# Schematic.net
KiCad netlist of a schematic drawn in Altium Designer
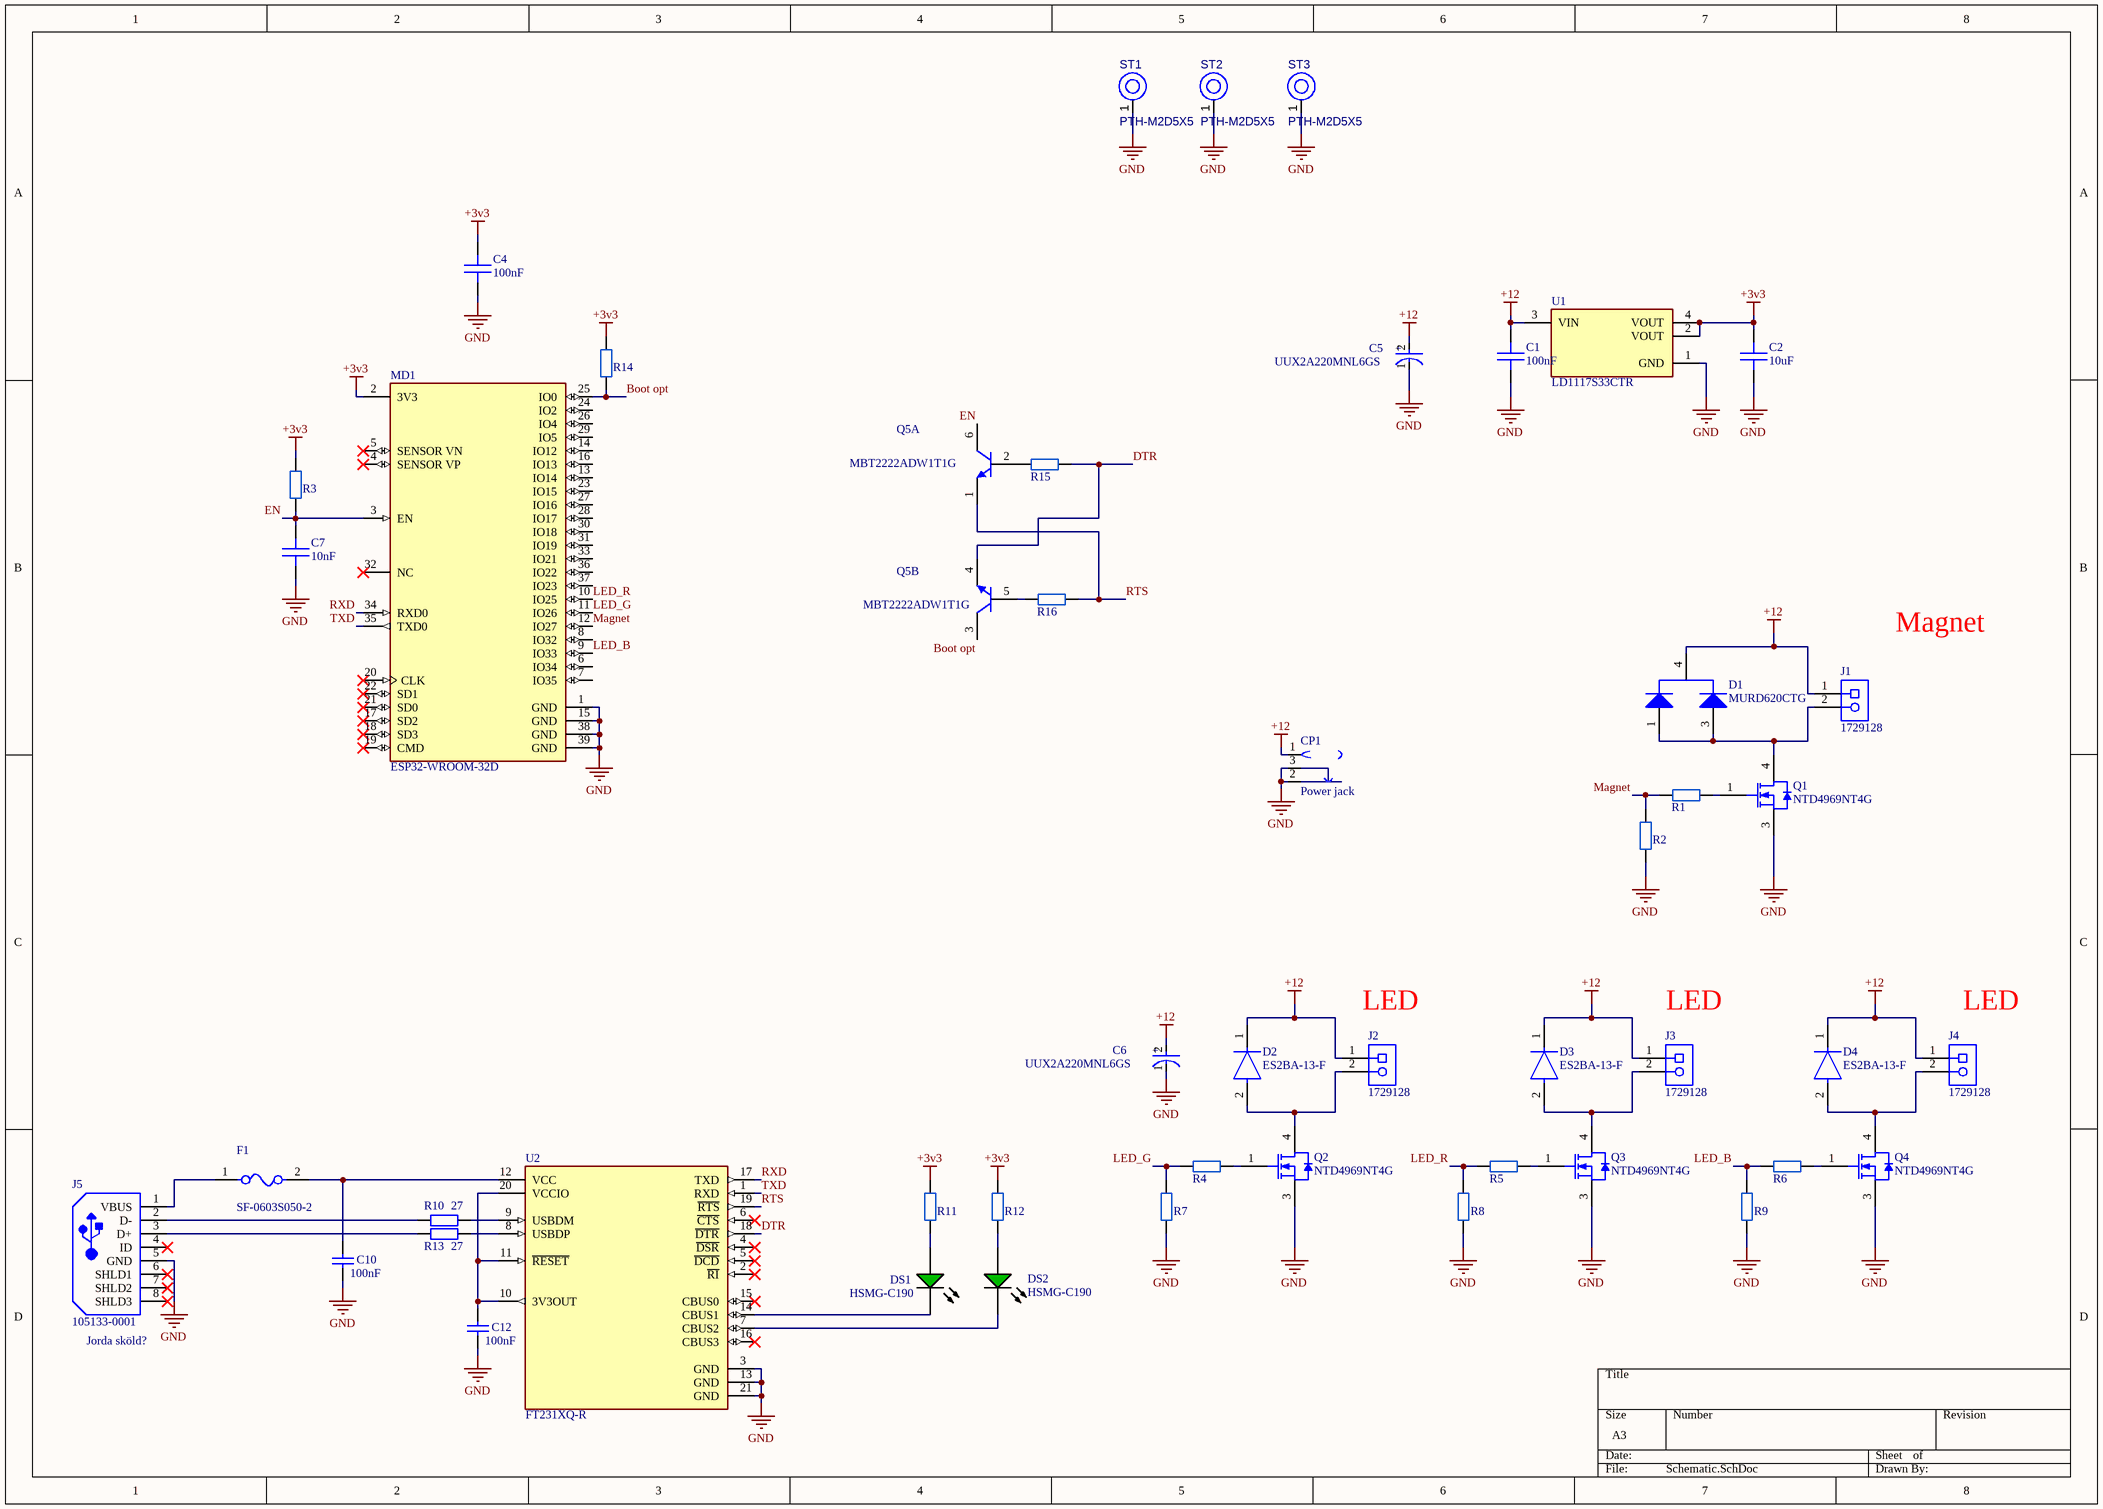
[diagram p0: Schematic.SchDoc]

(export (version "E")
  (design (tool "Eeschema 10.0.6"))
  (components
    (comp (ref "C1")
      (value "100nF")
      (footprint "C0603 (1608)")
      (fields (field (name "Comment") "Cap SMD"))
      (libsource (lib "Moto Symbol Lib") (part "Cap SMD"))
    )
    (comp (ref "C2")
      (value "10uF")
      (footprint "C0603 (1608)")
      (fields (field (name "Comment") "Cap SMD"))
      (libsource (lib "Moto Symbol Lib") (part "Cap SMD"))
    )
    (comp (ref "C4")
      (value "100nF")
      (footprint "C0603 (1608)")
      (fields (field (name "Comment") "Cap SMD"))
      (libsource (lib "Moto Symbol Lib") (part "Cap SMD"))
    )
    (comp (ref "C5")
      (value "UUX2A220MNL6GS")
      (footprint "FP-UUX2A220MNL6GS-MFG")
      (description "CAP ALUM 22UF 20% 100V SMD")
      (fields (field (name "TOLERANCE") "20%"))
      (libsource (lib "Altium Content Vault") (part "cf48714ba7e38822c1575c7ec0b6d1f"))
    )
    (comp (ref "C6")
      (value "UUX2A220MNL6GS")
      (footprint "FP-UUX2A220MNL6GS-MFG")
      (description "CAP ALUM 22UF 20% 100V SMD")
      (fields (field (name "TOLERANCE") "20%"))
      (libsource (lib "Altium Content Vault") (part "cf48714ba7e38822c1575c7ec0b6d1f"))
    )
    (comp (ref "C7")
      (value "10nF")
      (footprint "C0603 (1608)")
      (fields (field (name "Comment") "Cap SMD"))
      (libsource (lib "Moto Symbol Lib") (part "Cap SMD"))
    )
    (comp (ref "C10")
      (value "100nF")
      (footprint "C0603 (1608)")
      (description "Capacitor")
      (fields (field (name "PUBLISHER") "Altium Limited"))
      (libsource (lib "Miscellaneous Devices") (part "Cap"))
    )
    (comp (ref "C12")
      (value "100nF")
      (footprint "C0603 (1608)")
      (description "Capacitor")
      (fields (field (name "PUBLISHER") "Altium Limited"))
      (libsource (lib "Miscellaneous Devices") (part "Cap"))
    )
    (comp (ref "CP1")
      (value "Power jack")
      (footprint "CLIFF SMD KLD-0202 BARRELL JACK DC CONNECTOR 2.1mm")
      (description "Surface mounted DC barrell jack, KLD-0202 design")
      (libsource (lib "lokalib") (part "Barrel jack KLD-0202"))
    )
    (comp (ref "D1")
      (value "MURD620CTG")
      (footprint "ONSC-DPAK-3-369C-01_V")
      (description "SWITCHMODE(TM) Power Rectifier, 3-Pin DPAK, Pb-Free, Tube")
      (fields (field (name "MANUFACTURER") "On Semiconductor"))
      (libsource (lib "Altium Content Vault") (part "ONSC-D-A1A3K4-3_B"))
    )
    (comp (ref "D2")
      (value "ES2BA-13-F")
      (footprint "FP-SMA-MFG")
      (description "DIODE GEN PURP 100V 2A SMA")
      (fields
        (field (name "MANUFACTURER") "Diodes Inc.")
        (field (name "OCTOPART") "https://octopart.com/es2ba-13-f-diodes+inc.-14402013")
      )
      (libsource (lib "Altium Content Vault") (part "d7152d700b627762746794eb795d46e"))
    )
    (comp (ref "D3")
      (value "ES2BA-13-F")
      (footprint "FP-SMA-MFG")
      (description "DIODE GEN PURP 100V 2A SMA")
      (fields
        (field (name "MANUFACTURER") "Diodes Inc.")
        (field (name "OCTOPART") "https://octopart.com/es2ba-13-f-diodes+inc.-14402013")
      )
      (libsource (lib "Altium Content Vault") (part "d7152d700b627762746794eb795d46e"))
    )
    (comp (ref "D4")
      (value "ES2BA-13-F")
      (footprint "FP-SMA-MFG")
      (description "DIODE GEN PURP 100V 2A SMA")
      (fields
        (field (name "MANUFACTURER") "Diodes Inc.")
        (field (name "OCTOPART") "https://octopart.com/es2ba-13-f-diodes+inc.-14402013")
      )
      (libsource (lib "Altium Content Vault") (part "d7152d700b627762746794eb795d46e"))
    )
    (comp (ref "DS1")
      (value "HSMG-C190")
      (footprint "AVAG-HSMX-C190_V")
      (description "Chip LED, Green, 2.2 V, -40 to 85 degC, 2-Pin SMD, RoHS, Tape and Reel")
      (libsource (lib "Altium Content Vault") (part "LED-GREEN-AK-2"))
    )
    (comp (ref "DS2")
      (value "HSMG-C190")
      (footprint "AVAG-HSMX-C190_V")
      (description "Chip LED, Green, 2.2 V, -40 to 85 degC, 2-Pin SMD, RoHS, Tape and Reel")
      (libsource (lib "Altium Content Vault") (part "LED-GREEN-AK-2"))
    )
    (comp (ref "F1")
      (value "SF-0603S050-2")
      (footprint "FP-SF-0603S-MFG")
      (description "FUSE BOARD MNT 500MA 50VDC 0603")
      (fields
        (field (name "MANUFACTURER") "Bourns Inc.")
        (field (name "OCTOPART") "https://octopart.com/sf-0603s050-2-bourns-10486821")
      )
      (libsource (lib "Altium Content Vault") (part "5bcf9b9f640e542cf0359d10258e979"))
    )
    (comp (ref "J1")
      (value "1729128")
      (footprint "PHOE-1729128-2_V")
      (description "PCB Terminal Block, 13.5 A, 400 V, 2-Pin THD, RoHS, Bulk")
      (fields (field (name "MANUFACTURER") "Phoenix Contact"))
      (libsource (lib "Altium Content Vault") (part "CN-2P-F-R2"))
    )
    (comp (ref "J2")
      (value "1729128")
      (footprint "PHOE-1729128-2_V")
      (description "PCB Terminal Block, 13.5 A, 400 V, 2-Pin THD, RoHS, Bulk")
      (fields (field (name "MANUFACTURER") "Phoenix Contact"))
      (libsource (lib "Altium Content Vault") (part "CN-2P-F-R2"))
    )
    (comp (ref "J3")
      (value "1729128")
      (footprint "PHOE-1729128-2_V")
      (description "PCB Terminal Block, 13.5 A, 400 V, 2-Pin THD, RoHS, Bulk")
      (fields (field (name "MANUFACTURER") "Phoenix Contact"))
      (libsource (lib "Altium Content Vault") (part "CN-2P-F-R2"))
    )
    (comp (ref "J4")
      (value "1729128")
      (footprint "PHOE-1729128-2_V")
      (description "PCB Terminal Block, 13.5 A, 400 V, 2-Pin THD, RoHS, Bulk")
      (fields (field (name "MANUFACTURER") "Phoenix Contact"))
      (libsource (lib "Altium Content Vault") (part "CN-2P-F-R2"))
    )
    (comp (ref "J5")
      (value "105133-0001")
      (footprint "MOLX-105133-0001_V")
      (description "Micro-USB B Receptacle, Vertical, -30 to 85 degC, 5-Pin SMD, RoHS, Tape and Reel")
      (fields (field (name "MANUFACTURER") "Molex"))
      (libsource (lib "Altium Content Vault") (part "USB-5-3SHLD"))
    )
    (comp (ref "MD1")
      (value "ESP32-WROOM-32D")
      (footprint "FP-ESP32-WROOM-32D-MFG")
      (description "WIFI MODULE 32MBITS SPI FLASH")
      (fields
        (field (name "OCTOPART") "https://octopart.com/esp32-wroom-32d-espressif+systems-91040050")
        (field (name "MANUFACTURER") "Espressif Systems")
      )
      (libsource (lib "Altium Content Vault") (part "a031a76f8c27026a7a7f4657ff233a3"))
    )
    (comp (ref "Q1")
      (value "NTD4969NT4G")
      (footprint "ONSC-DPAK-3-369AA-01_V")
      (description "Power MOSFET, 30 V, 41 A, Single N-Channel, 3-Pin DPAK, Pb-Free, Tape and Reel")
      (fields (field (name "MANUFACTURER") "On Semiconductor"))
      (libsource (lib "Altium Content Vault") (part "ONSC-NMOS-G1S3D4-3_B"))
    )
    (comp (ref "Q2")
      (value "NTD4969NT4G")
      (footprint "ONSC-DPAK-3-369AA-01_V")
      (description "Power MOSFET, 30 V, 41 A, Single N-Channel, 3-Pin DPAK, Pb-Free, Tape and Reel")
      (fields (field (name "MANUFACTURER") "On Semiconductor"))
      (libsource (lib "Altium Content Vault") (part "ONSC-NMOS-G1S3D4-3_B"))
    )
    (comp (ref "Q3")
      (value "NTD4969NT4G")
      (footprint "ONSC-DPAK-3-369AA-01_V")
      (description "Power MOSFET, 30 V, 41 A, Single N-Channel, 3-Pin DPAK, Pb-Free, Tape and Reel")
      (fields (field (name "MANUFACTURER") "On Semiconductor"))
      (libsource (lib "Altium Content Vault") (part "ONSC-NMOS-G1S3D4-3_B"))
    )
    (comp (ref "Q4")
      (value "NTD4969NT4G")
      (footprint "ONSC-DPAK-3-369AA-01_V")
      (description "Power MOSFET, 30 V, 41 A, Single N-Channel, 3-Pin DPAK, Pb-Free, Tape and Reel")
      (fields (field (name "MANUFACTURER") "On Semiconductor"))
      (libsource (lib "Altium Content Vault") (part "ONSC-NMOS-G1S3D4-3_B"))
    )
    (comp (ref "Q5")
      (value "MBT2222ADW1T1G")
      (footprint "ONSC-SOT-363-6-419B-02_V")
      (description "General Purpose Transistor, NPN Silicon, 6-Pin SOT-363, Pb-Free, Tape and Reel")
      (fields (field (name "MANUFACTURER") "On Semiconductor"))
      (libsource (lib "Altium Content Vault") (part "ONSC-NPN_NPN-6_F"))
    )
    (comp (ref "R1")
      (value "Res")
      (footprint "R0603 (1608)")
      (libsource (lib "Moto Symbol Lib") (part "Resistor EU"))
    )
    (comp (ref "R2")
      (value "Res")
      (footprint "R0603 (1608)")
      (libsource (lib "Moto Symbol Lib") (part "Resistor EU"))
    )
    (comp (ref "R3")
      (value "Res")
      (footprint "R0603 (1608)")
      (libsource (lib "Moto Symbol Lib") (part "Resistor EU"))
    )
    (comp (ref "R4")
      (value "Res")
      (footprint "R0603 (1608)")
      (libsource (lib "Moto Symbol Lib") (part "Resistor EU"))
    )
    (comp (ref "R5")
      (value "Res")
      (footprint "R0603 (1608)")
      (libsource (lib "Moto Symbol Lib") (part "Resistor EU"))
    )
    (comp (ref "R6")
      (value "Res")
      (footprint "R0603 (1608)")
      (libsource (lib "Moto Symbol Lib") (part "Resistor EU"))
    )
    (comp (ref "R7")
      (value "Res")
      (footprint "R0603 (1608)")
      (libsource (lib "Moto Symbol Lib") (part "Resistor EU"))
    )
    (comp (ref "R8")
      (value "Res")
      (footprint "R0603 (1608)")
      (libsource (lib "Moto Symbol Lib") (part "Resistor EU"))
    )
    (comp (ref "R9")
      (value "Res")
      (footprint "R0603 (1608)")
      (libsource (lib "Moto Symbol Lib") (part "Resistor EU"))
    )
    (comp (ref "R10")
      (value "27")
      (footprint "R0603 (1608)")
      (description "Resistor")
      (fields (field (name "PUBLISHER") "Altium Limited"))
      (libsource (lib "Miscellaneous Devices") (part "Res2"))
    )
    (comp (ref "R11")
      (value "Res")
      (footprint "R0603 (1608)")
      (libsource (lib "Moto Symbol Lib") (part "Resistor EU"))
    )
    (comp (ref "R12")
      (value "Res")
      (footprint "R0603 (1608)")
      (libsource (lib "Moto Symbol Lib") (part "Resistor EU"))
    )
    (comp (ref "R13")
      (value "27")
      (footprint "R0603 (1608)")
      (description "Resistor")
      (fields (field (name "PUBLISHER") "Altium Limited"))
      (libsource (lib "Miscellaneous Devices") (part "Res2"))
    )
    (comp (ref "R14")
      (value "Res")
      (footprint "R0603 (1608)")
      (libsource (lib "Moto Symbol Lib") (part "Resistor EU"))
    )
    (comp (ref "R15")
      (value "Res")
      (footprint "R0603 (1608)")
      (libsource (lib "Moto Symbol Lib") (part "Resistor EU"))
    )
    (comp (ref "R16")
      (value "Res")
      (footprint "R0603 (1608)")
      (libsource (lib "Moto Symbol Lib") (part "Resistor EU"))
    )
    (comp (ref "ST1")
      (value "PTH-M2D5X5")
      (footprint "PTH-M2D5X5")
      (description "M2 PTH (2.5mm), 5mm pad")
      (libsource (lib "ETA - E-sektionsens Teletekniska Avdelning") (part "CMP-00028-00000-1"))
    )
    (comp (ref "ST2")
      (value "PTH-M2D5X5")
      (footprint "PTH-M2D5X5")
      (description "M2 PTH (2.5mm), 5mm pad")
      (libsource (lib "ETA - E-sektionsens Teletekniska Avdelning") (part "CMP-00028-00000-1"))
    )
    (comp (ref "ST3")
      (value "PTH-M2D5X5")
      (footprint "PTH-M2D5X5")
      (description "M2 PTH (2.5mm), 5mm pad")
      (libsource (lib "ETA - E-sektionsens Teletekniska Avdelning") (part "CMP-00028-00000-1"))
    )
    (comp (ref "U1")
      (value "LD1117S33CTR")
      (footprint "FP-SOT-223-0046067_14-MFG")
      (description "IC REG LINEAR 3.3V 800MA SOT223")
      (libsource (lib "Altium Content Vault") (part "7818869c5c16ceab15634627166a29d"))
    )
    (comp (ref "U2")
      (value "FT231XQ-R")
      (footprint "FP-QFN-20-MFG")
      (description "IC USB SERIAL FULL UART 20QFN")
      (libsource (lib "Altium Content Vault") (part "1a58eaec777a01ae16a7011961d8d4e"))
    )
  )
  (nets
    (net (code "1") (name "+3v3") (class "Default")
      (node (ref "C2") (pin "2") (pinfunction "2_2") (pintype "power_in"))
      (node (ref "C4") (pin "2") (pinfunction "2_2") (pintype "power_in"))
      (node (ref "MD1") (pin "2") (pinfunction "3V3_2") (pintype "power_in"))
      (node (ref "R11") (pin "2") (pinfunction "2_2") (pintype "power_in"))
      (node (ref "R12") (pin "2") (pinfunction "2_2") (pintype "power_in"))
      (node (ref "R14") (pin "1") (pinfunction "1_1") (pintype "power_in"))
      (node (ref "R3") (pin "1") (pinfunction "1_1") (pintype "power_in"))
      (node (ref "U1") (pin "2") (pinfunction "VOUT_2") (pintype "power_in"))
      (node (ref "U1") (pin "4") (pinfunction "VOUT_4") (pintype "power_in"))
    )
    (net (code "2") (name "+12") (class "Default")
      (node (ref "C1") (pin "2") (pinfunction "2_2") (pintype "power_in"))
      (node (ref "C5") (pin "2") (pinfunction "A_2") (pintype "passive"))
      (node (ref "C6") (pin "2") (pinfunction "A_2") (pintype "passive"))
      (node (ref "CP1") (pin "1") (pintype "passive"))
      (node (ref "D1") (pin "4") (pinfunction "K_4") (pintype "passive"))
      (node (ref "D2") (pin "1") (pinfunction "C_1") (pintype "passive"))
      (node (ref "D3") (pin "1") (pinfunction "C_1") (pintype "passive"))
      (node (ref "D4") (pin "1") (pinfunction "C_1") (pintype "passive"))
      (node (ref "J1") (pin "1") (pinfunction "1_1") (pintype "passive"))
      (node (ref "J2") (pin "1") (pinfunction "1_1") (pintype "passive"))
      (node (ref "J3") (pin "1") (pinfunction "1_1") (pintype "passive"))
      (node (ref "J4") (pin "1") (pinfunction "1_1") (pintype "passive"))
      (node (ref "U1") (pin "3") (pinfunction "VIN_3") (pintype "power_in"))
    )
    (net (code "3") (name "/Boot opt") (class "Default")
      (node (ref "MD1") (pin "25") (pinfunction "IO0_25") (pintype "bidirectional"))
      (node (ref "Q5") (pin "3") (pinfunction "C_3") (pintype "passive"))
      (node (ref "R14") (pin "2") (pinfunction "2_2") (pintype "power_in"))
    )
    (net (code "4") (name "/DTR") (class "Default")
      (node (ref "Q5") (pin "4") (pinfunction "E_4") (pintype "passive"))
      (node (ref "R15") (pin "2") (pinfunction "2_2") (pintype "power_in"))
      (node (ref "U2") (pin "18") (pinfunction "~{DTR}_18") (pintype "output"))
    )
    (net (code "5") (name "/EN") (class "Default")
      (node (ref "C7") (pin "2") (pinfunction "2_2") (pintype "power_in"))
      (node (ref "MD1") (pin "3") (pinfunction "EN_3") (pintype "input"))
      (node (ref "Q5") (pin "6") (pinfunction "C_6") (pintype "passive"))
      (node (ref "R3") (pin "2") (pinfunction "2_2") (pintype "power_in"))
    )
    (net (code "6") (name "/LED_B") (class "Default")
      (node (ref "MD1") (pin "9") (pinfunction "IO33_9") (pintype "bidirectional"))
      (node (ref "R6") (pin "2") (pinfunction "2_2") (pintype "power_in"))
      (node (ref "R9") (pin "2") (pinfunction "2_2") (pintype "power_in"))
    )
    (net (code "7") (name "/LED_G") (class "Default")
      (node (ref "MD1") (pin "11") (pinfunction "IO26_11") (pintype "bidirectional"))
      (node (ref "R4") (pin "2") (pinfunction "2_2") (pintype "power_in"))
      (node (ref "R7") (pin "2") (pinfunction "2_2") (pintype "power_in"))
    )
    (net (code "8") (name "/LED_R") (class "Default")
      (node (ref "MD1") (pin "10") (pinfunction "IO25_10") (pintype "bidirectional"))
      (node (ref "R5") (pin "2") (pinfunction "2_2") (pintype "power_in"))
      (node (ref "R8") (pin "1") (pinfunction "1_1") (pintype "power_in"))
    )
    (net (code "9") (name "/Magnet") (class "Default")
      (node (ref "MD1") (pin "12") (pinfunction "IO27_12") (pintype "bidirectional"))
      (node (ref "R1") (pin "2") (pinfunction "2_2") (pintype "power_in"))
      (node (ref "R2") (pin "2") (pinfunction "2_2") (pintype "power_in"))
    )
    (net (code "10") (name "/RTS") (class "Default")
      (node (ref "Q5") (pin "1") (pinfunction "E_1") (pintype "passive"))
      (node (ref "R16") (pin "2") (pinfunction "2_2") (pintype "power_in"))
      (node (ref "U2") (pin "19") (pinfunction "~{RTS}_19") (pintype "output"))
    )
    (net (code "11") (name "/RXD") (class "Default")
      (node (ref "MD1") (pin "34") (pinfunction "RXD0_34") (pintype "input"))
      (node (ref "U2") (pin "17") (pinfunction "TXD_17") (pintype "output"))
    )
    (net (code "12") (name "/TXD") (class "Default")
      (node (ref "MD1") (pin "35") (pinfunction "TXD0_35") (pintype "output"))
      (node (ref "U2") (pin "1") (pinfunction "RXD_1") (pintype "input"))
    )
    (net (code "13") (name "GND") (class "Default")
      (node (ref "C1") (pin "1") (pinfunction "1_1") (pintype "power_in"))
      (node (ref "C10") (pin "1") (pinfunction "1_1") (pintype "passive"))
      (node (ref "C12") (pin "1") (pinfunction "1_1") (pintype "passive"))
      (node (ref "C2") (pin "1") (pinfunction "1_1") (pintype "power_in"))
      (node (ref "C4") (pin "1") (pinfunction "1_1") (pintype "power_in"))
      (node (ref "C5") (pin "1") (pinfunction "C_1") (pintype "passive"))
      (node (ref "C6") (pin "1") (pinfunction "C_1") (pintype "passive"))
      (node (ref "C7") (pin "1") (pinfunction "1_1") (pintype "power_in"))
      (node (ref "CP1") (pin "2") (pintype "passive"))
      (node (ref "CP1") (pin "3") (pintype "passive"))
      (node (ref "J5") (pin "5") (pinfunction "GND_5") (pintype "passive"))
      (node (ref "MD1") (pin "1") (pinfunction "GND_1") (pintype "power_in"))
      (node (ref "MD1") (pin "15") (pinfunction "GND_15") (pintype "power_in"))
      (node (ref "MD1") (pin "38") (pinfunction "GND_38") (pintype "power_in"))
      (node (ref "MD1") (pin "39") (pinfunction "GND_39") (pintype "power_in"))
      (node (ref "Q1") (pin "3") (pinfunction "S_3") (pintype "passive"))
      (node (ref "Q2") (pin "3") (pinfunction "S_3") (pintype "passive"))
      (node (ref "Q3") (pin "3") (pinfunction "S_3") (pintype "passive"))
      (node (ref "Q4") (pin "3") (pinfunction "S_3") (pintype "passive"))
      (node (ref "R2") (pin "1") (pinfunction "1_1") (pintype "power_in"))
      (node (ref "R7") (pin "1") (pinfunction "1_1") (pintype "power_in"))
      (node (ref "R8") (pin "2") (pinfunction "2_2") (pintype "power_in"))
      (node (ref "R9") (pin "1") (pinfunction "1_1") (pintype "power_in"))
      (node (ref "ST1") (pin "1") (pinfunction "H1_1") (pintype "passive"))
      (node (ref "ST2") (pin "1") (pinfunction "H1_1") (pintype "passive"))
      (node (ref "ST3") (pin "1") (pinfunction "H1_1") (pintype "passive"))
      (node (ref "U1") (pin "1") (pinfunction "GND_1") (pintype "power_in"))
      (node (ref "U2") (pin "13") (pinfunction "GND_13") (pintype "open_emitter"))
      (node (ref "U2") (pin "21") (pinfunction "GND_21") (pintype "power_in"))
      (node (ref "U2") (pin "3") (pinfunction "GND_3") (pintype "power_in"))
    )
    (net (code "14") (name "Net-(D1-A1)") (class "Default")
      (node (ref "D1") (pin "1") (pinfunction "A1_1") (pintype "passive"))
      (node (ref "D1") (pin "3") (pinfunction "A2_3") (pintype "passive"))
      (node (ref "J1") (pin "2") (pinfunction "2_2") (pintype "passive"))
      (node (ref "Q1") (pin "4") (pinfunction "D_4") (pintype "passive"))
    )
    (net (code "15") (name "Net-(D2-A)") (class "Default")
      (node (ref "D2") (pin "2") (pinfunction "A_2") (pintype "passive"))
      (node (ref "J2") (pin "2") (pinfunction "2_2") (pintype "passive"))
      (node (ref "Q2") (pin "4") (pinfunction "D_4") (pintype "passive"))
    )
    (net (code "16") (name "Net-(D3-A)") (class "Default")
      (node (ref "D3") (pin "2") (pinfunction "A_2") (pintype "passive"))
      (node (ref "J3") (pin "2") (pinfunction "2_2") (pintype "passive"))
      (node (ref "Q3") (pin "4") (pinfunction "D_4") (pintype "passive"))
    )
    (net (code "17") (name "Net-(D4-A)") (class "Default")
      (node (ref "D4") (pin "2") (pinfunction "A_2") (pintype "passive"))
      (node (ref "J4") (pin "2") (pinfunction "2_2") (pintype "passive"))
      (node (ref "Q4") (pin "4") (pinfunction "D_4") (pintype "passive"))
    )
    (net (code "18") (name "Net-(DS1-A)") (class "Default")
      (node (ref "DS1") (pin "1") (pinfunction "A_1") (pintype "passive"))
      (node (ref "R11") (pin "1") (pinfunction "1_1") (pintype "power_in"))
    )
    (net (code "19") (name "Net-(DS1-K)") (class "Default")
      (node (ref "DS1") (pin "2") (pinfunction "K_2") (pintype "passive"))
      (node (ref "U2") (pin "14") (pinfunction "CBUS1_14") (pintype "bidirectional"))
    )
    (net (code "20") (name "Net-(DS2-A)") (class "Default")
      (node (ref "DS2") (pin "1") (pinfunction "A_1") (pintype "passive"))
      (node (ref "R12") (pin "1") (pinfunction "1_1") (pintype "power_in"))
    )
    (net (code "21") (name "Net-(DS2-K)") (class "Default")
      (node (ref "DS2") (pin "2") (pinfunction "K_2") (pintype "passive"))
      (node (ref "U2") (pin "7") (pinfunction "CBUS2_7") (pintype "bidirectional"))
    )
    (net (code "22") (name "Net-(J5-D+)") (class "Default")
      (node (ref "J5") (pin "3") (pinfunction "D+_3") (pintype "passive"))
      (node (ref "R13") (pin "1") (pinfunction "1_1") (pintype "passive"))
    )
    (net (code "23") (name "Net-(J5-D-)") (class "Default")
      (node (ref "J5") (pin "2") (pinfunction "D-_2") (pintype "passive"))
      (node (ref "R10") (pin "1") (pinfunction "1_1") (pintype "passive"))
    )
    (net (code "24") (name "Net-(J5-VBUS)") (class "Default")
      (node (ref "F1") (pin "1") (pinfunction "1_1") (pintype "passive"))
      (node (ref "J5") (pin "1") (pinfunction "VBUS_1") (pintype "passive"))
    )
    (net (code "25") (name "Net-(Q1-G)") (class "Default")
      (node (ref "Q1") (pin "1") (pinfunction "G_1") (pintype "passive"))
      (node (ref "R1") (pin "1") (pinfunction "1_1") (pintype "power_in"))
    )
    (net (code "26") (name "Net-(Q2-G)") (class "Default")
      (node (ref "Q2") (pin "1") (pinfunction "G_1") (pintype "passive"))
      (node (ref "R4") (pin "1") (pinfunction "1_1") (pintype "power_in"))
    )
    (net (code "27") (name "Net-(Q3-G)") (class "Default")
      (node (ref "Q3") (pin "1") (pinfunction "G_1") (pintype "passive"))
      (node (ref "R5") (pin "1") (pinfunction "1_1") (pintype "power_in"))
    )
    (net (code "28") (name "Net-(Q4-G)") (class "Default")
      (node (ref "Q4") (pin "1") (pinfunction "G_1") (pintype "passive"))
      (node (ref "R6") (pin "1") (pinfunction "1_1") (pintype "power_in"))
    )
    (net (code "29") (name "Net-(Q5A-B)") (class "Default")
      (node (ref "Q5") (pin "2") (pinfunction "B_2") (pintype "passive"))
      (node (ref "R15") (pin "1") (pinfunction "1_1") (pintype "power_in"))
    )
    (net (code "30") (name "Net-(Q5B-B)") (class "Default")
      (node (ref "Q5") (pin "5") (pinfunction "B_5") (pintype "passive"))
      (node (ref "R16") (pin "1") (pinfunction "1_1") (pintype "power_in"))
    )
    (net (code "31") (name "Net-(U2-3V3OUT)") (class "Default")
      (node (ref "C12") (pin "2") (pinfunction "2_2") (pintype "passive"))
      (node (ref "U2") (pin "10") (pinfunction "3V3OUT_10") (pintype "output"))
      (node (ref "U2") (pin "11") (pinfunction "~{RESET}_11") (pintype "input"))
      (node (ref "U2") (pin "20") (pinfunction "VCCIO_20") (pintype "power_in"))
    )
    (net (code "32") (name "Net-(U2-USBDM)") (class "Default")
      (node (ref "R10") (pin "2") (pinfunction "2_2") (pintype "passive"))
      (node (ref "U2") (pin "9") (pinfunction "USBDM_9") (pintype "input"))
    )
    (net (code "33") (name "Net-(U2-USBDP)") (class "Default")
      (node (ref "R13") (pin "2") (pinfunction "2_2") (pintype "passive"))
      (node (ref "U2") (pin "8") (pinfunction "USBDP_8") (pintype "input"))
    )
    (net (code "34") (name "Net-(U2-VCC)") (class "Default")
      (node (ref "C10") (pin "2") (pinfunction "2_2") (pintype "passive"))
      (node (ref "F1") (pin "2") (pinfunction "2_2") (pintype "passive"))
      (node (ref "U2") (pin "12") (pinfunction "VCC_12") (pintype "power_in"))
    )
    (net (code "35") (name "unconnected-(J5-ID-Pad4)") (class "Default")
      (node (ref "J5") (pin "4") (pinfunction "ID_4") (pintype "passive+no_connect"))
    )
    (net (code "36") (name "unconnected-(J5-SHLD1-Pad6)") (class "Default")
      (node (ref "J5") (pin "6") (pinfunction "SHLD1_6") (pintype "passive+no_connect"))
    )
    (net (code "37") (name "unconnected-(J5-SHLD2-Pad7)") (class "Default")
      (node (ref "J5") (pin "7") (pinfunction "SHLD2_7") (pintype "passive+no_connect"))
    )
    (net (code "38") (name "unconnected-(J5-SHLD3-Pad8)") (class "Default")
      (node (ref "J5") (pin "8") (pinfunction "SHLD3_8") (pintype "passive+no_connect"))
    )
    (net (code "39") (name "unconnected-(MD1-CLK-Pad20)") (class "Default")
      (node (ref "MD1") (pin "20") (pinfunction "CLK_20") (pintype "input+no_connect"))
    )
    (net (code "40") (name "unconnected-(MD1-CMD-Pad19)") (class "Default")
      (node (ref "MD1") (pin "19") (pinfunction "CMD_19") (pintype "bidirectional+no_connect"))
    )
    (net (code "41") (name "unconnected-(MD1-IO2-Pad24)") (class "Default")
      (node (ref "MD1") (pin "24") (pinfunction "IO2_24") (pintype "bidirectional"))
    )
    (net (code "42") (name "unconnected-(MD1-IO4-Pad26)") (class "Default")
      (node (ref "MD1") (pin "26") (pinfunction "IO4_26") (pintype "bidirectional"))
    )
    (net (code "43") (name "unconnected-(MD1-IO5-Pad29)") (class "Default")
      (node (ref "MD1") (pin "29") (pinfunction "IO5_29") (pintype "bidirectional"))
    )
    (net (code "44") (name "unconnected-(MD1-IO12-Pad14)") (class "Default")
      (node (ref "MD1") (pin "14") (pinfunction "IO12_14") (pintype "bidirectional"))
    )
    (net (code "45") (name "unconnected-(MD1-IO13-Pad16)") (class "Default")
      (node (ref "MD1") (pin "16") (pinfunction "IO13_16") (pintype "bidirectional"))
    )
    (net (code "46") (name "unconnected-(MD1-IO14-Pad13)") (class "Default")
      (node (ref "MD1") (pin "13") (pinfunction "IO14_13") (pintype "bidirectional"))
    )
    (net (code "47") (name "unconnected-(MD1-IO15-Pad23)") (class "Default")
      (node (ref "MD1") (pin "23") (pinfunction "IO15_23") (pintype "bidirectional"))
    )
    (net (code "48") (name "unconnected-(MD1-IO16-Pad27)") (class "Default")
      (node (ref "MD1") (pin "27") (pinfunction "IO16_27") (pintype "bidirectional"))
    )
    (net (code "49") (name "unconnected-(MD1-IO17-Pad28)") (class "Default")
      (node (ref "MD1") (pin "28") (pinfunction "IO17_28") (pintype "bidirectional"))
    )
    (net (code "50") (name "unconnected-(MD1-IO18-Pad30)") (class "Default")
      (node (ref "MD1") (pin "30") (pinfunction "IO18_30") (pintype "bidirectional"))
    )
    (net (code "51") (name "unconnected-(MD1-IO19-Pad31)") (class "Default")
      (node (ref "MD1") (pin "31") (pinfunction "IO19_31") (pintype "bidirectional"))
    )
    (net (code "52") (name "unconnected-(MD1-IO21-Pad33)") (class "Default")
      (node (ref "MD1") (pin "33") (pinfunction "IO21_33") (pintype "bidirectional"))
    )
    (net (code "53") (name "unconnected-(MD1-IO22-Pad36)") (class "Default")
      (node (ref "MD1") (pin "36") (pinfunction "IO22_36") (pintype "bidirectional"))
    )
    (net (code "54") (name "unconnected-(MD1-IO23-Pad37)") (class "Default")
      (node (ref "MD1") (pin "37") (pinfunction "IO23_37") (pintype "bidirectional"))
    )
    (net (code "55") (name "unconnected-(MD1-IO32-Pad8)") (class "Default")
      (node (ref "MD1") (pin "8") (pinfunction "IO32_8") (pintype "bidirectional"))
    )
    (net (code "56") (name "unconnected-(MD1-IO34-Pad6)") (class "Default")
      (node (ref "MD1") (pin "6") (pinfunction "IO34_6") (pintype "bidirectional"))
    )
    (net (code "57") (name "unconnected-(MD1-IO35-Pad7)") (class "Default")
      (node (ref "MD1") (pin "7") (pinfunction "IO35_7") (pintype "bidirectional"))
    )
    (net (code "58") (name "unconnected-(MD1-NC-Pad32)") (class "Default")
      (node (ref "MD1") (pin "32") (pinfunction "NC_32") (pintype "passive+no_connect"))
    )
    (net (code "59") (name "unconnected-(MD1-SD0-Pad21)") (class "Default")
      (node (ref "MD1") (pin "21") (pinfunction "SD0_21") (pintype "bidirectional+no_connect"))
    )
    (net (code "60") (name "unconnected-(MD1-SD1-Pad22)") (class "Default")
      (node (ref "MD1") (pin "22") (pinfunction "SD1_22") (pintype "bidirectional+no_connect"))
    )
    (net (code "61") (name "unconnected-(MD1-SD2-Pad17)") (class "Default")
      (node (ref "MD1") (pin "17") (pinfunction "SD2_17") (pintype "bidirectional+no_connect"))
    )
    (net (code "62") (name "unconnected-(MD1-SD3-Pad18)") (class "Default")
      (node (ref "MD1") (pin "18") (pinfunction "SD3_18") (pintype "bidirectional+no_connect"))
    )
    (net (code "63") (name "unconnected-(MD1-SENSOR_VN-Pad5)") (class "Default")
      (node (ref "MD1") (pin "5") (pinfunction "SENSOR_VN_5") (pintype "bidirectional+no_connect"))
    )
    (net (code "64") (name "unconnected-(MD1-SENSOR_VP-Pad4)") (class "Default")
      (node (ref "MD1") (pin "4") (pinfunction "SENSOR_VP_4") (pintype "bidirectional+no_connect"))
    )
    (net (code "65") (name "unconnected-(U2-CBUS0-Pad15)") (class "Default")
      (node (ref "U2") (pin "15") (pinfunction "CBUS0_15") (pintype "bidirectional+no_connect"))
    )
    (net (code "66") (name "unconnected-(U2-CBUS3-Pad16)") (class "Default")
      (node (ref "U2") (pin "16") (pinfunction "CBUS3_16") (pintype "bidirectional+no_connect"))
    )
    (net (code "67") (name "unconnected-(U2-~{CTS}-Pad6)") (class "Default")
      (node (ref "U2") (pin "6") (pinfunction "~{CTS}_6") (pintype "input+no_connect"))
    )
    (net (code "68") (name "unconnected-(U2-~{DCD}-Pad5)") (class "Default")
      (node (ref "U2") (pin "5") (pinfunction "~{DCD}_5") (pintype "input+no_connect"))
    )
    (net (code "69") (name "unconnected-(U2-~{DSR}-Pad4)") (class "Default")
      (node (ref "U2") (pin "4") (pinfunction "~{DSR}_4") (pintype "input+no_connect"))
    )
    (net (code "70") (name "unconnected-(U2-~{RI}-Pad2)") (class "Default")
      (node (ref "U2") (pin "2") (pinfunction "~{RI}_2") (pintype "input+no_connect"))
    )
  )
)
